# big-module-test1.net
KiCad netlist of a schematic drawn in EAGLE
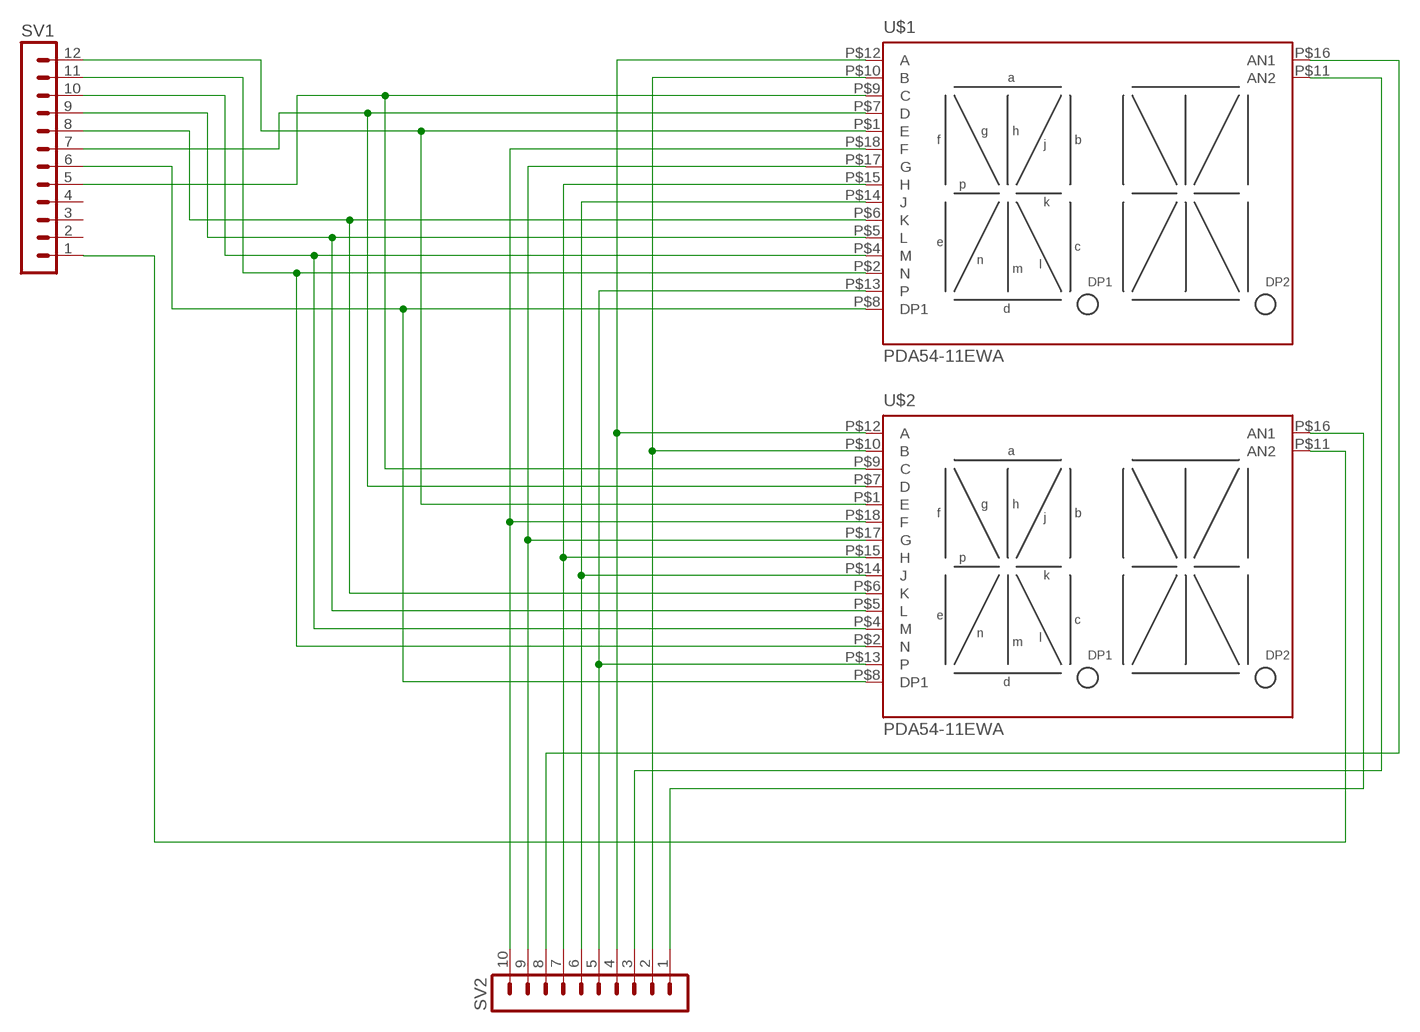
[diagram p0: schematic, sheet 1]

(export (version "E")
  (design (tool "Eeschema 10.0.6"))
  (components
    (comp (ref "SV1")
      (value "MA12-1W")
      (footprint "eagle-import:MA12-1W")
      (libsource (lib "eagle-import") (part "MA12-1W"))
    )
    (comp (ref "SV2")
      (value "MA10-1")
      (footprint "eagle-import:MA10-1")
      (libsource (lib "eagle-import") (part "MA10-1"))
    )
    (comp (ref "U$1")
      (value "PDA54-11EWA")
      (footprint "eagle-import:PDA54-11XX")
      (libsource (lib "eagle-import") (part "PDA54-11EWA"))
    )
    (comp (ref "U$2")
      (value "PDA54-11EWA")
      (footprint "eagle-import:PDA54-11XX")
      (libsource (lib "eagle-import") (part "PDA54-11EWA"))
    )
  )
  (nets
    (net (code "1") (name "Net-(U$1-A)") (class "Default")
      (node (ref "SV2") (pin "4") (pinfunction "4_4") (pintype "passive"))
      (node (ref "U$1") (pin "P$12") (pinfunction "A_P$12") (pintype "passive"))
      (node (ref "U$2") (pin "P$12") (pinfunction "A_P$12") (pintype "passive"))
    )
    (net (code "2") (name "Net-(U$1-AN1)") (class "Default")
      (node (ref "SV2") (pin "8") (pinfunction "8_8") (pintype "passive"))
      (node (ref "U$1") (pin "P$16") (pinfunction "AN1_P$16") (pintype "passive"))
    )
    (net (code "3") (name "Net-(U$1-AN2)") (class "Default")
      (node (ref "SV2") (pin "3") (pinfunction "3_3") (pintype "passive"))
      (node (ref "U$1") (pin "P$11") (pinfunction "AN2_P$11") (pintype "passive"))
    )
    (net (code "4") (name "Net-(U$1-B)") (class "Default")
      (node (ref "SV2") (pin "2") (pinfunction "2_2") (pintype "passive"))
      (node (ref "U$1") (pin "P$10") (pinfunction "B_P$10") (pintype "passive"))
      (node (ref "U$2") (pin "P$10") (pinfunction "B_P$10") (pintype "passive"))
    )
    (net (code "5") (name "Net-(U$1-C)") (class "Default")
      (node (ref "SV1") (pin "5") (pinfunction "5_5") (pintype "passive"))
      (node (ref "U$1") (pin "P$9") (pinfunction "C_P$9") (pintype "passive"))
      (node (ref "U$2") (pin "P$9") (pinfunction "C_P$9") (pintype "passive"))
    )
    (net (code "6") (name "Net-(U$1-D)") (class "Default")
      (node (ref "SV1") (pin "7") (pinfunction "7_7") (pintype "passive"))
      (node (ref "U$1") (pin "P$7") (pinfunction "D_P$7") (pintype "passive"))
      (node (ref "U$2") (pin "P$7") (pinfunction "D_P$7") (pintype "passive"))
    )
    (net (code "7") (name "Net-(U$1-DP1)") (class "Default")
      (node (ref "SV1") (pin "6") (pinfunction "6_6") (pintype "passive"))
      (node (ref "U$1") (pin "P$8") (pinfunction "DP1_P$8") (pintype "passive"))
      (node (ref "U$2") (pin "P$8") (pinfunction "DP1_P$8") (pintype "passive"))
    )
    (net (code "8") (name "Net-(U$1-E)") (class "Default")
      (node (ref "SV1") (pin "12") (pinfunction "12_12") (pintype "passive"))
      (node (ref "U$1") (pin "P$1") (pinfunction "E_P$1") (pintype "passive"))
      (node (ref "U$2") (pin "P$1") (pinfunction "E_P$1") (pintype "passive"))
    )
    (net (code "9") (name "Net-(U$1-F)") (class "Default")
      (node (ref "SV2") (pin "10") (pinfunction "10_10") (pintype "passive"))
      (node (ref "U$1") (pin "P$18") (pinfunction "F_P$18") (pintype "passive"))
      (node (ref "U$2") (pin "P$18") (pinfunction "F_P$18") (pintype "passive"))
    )
    (net (code "10") (name "Net-(U$1-G)") (class "Default")
      (node (ref "SV2") (pin "9") (pinfunction "9_9") (pintype "passive"))
      (node (ref "U$1") (pin "P$17") (pinfunction "G_P$17") (pintype "passive"))
      (node (ref "U$2") (pin "P$17") (pinfunction "G_P$17") (pintype "passive"))
    )
    (net (code "11") (name "Net-(U$1-H)") (class "Default")
      (node (ref "SV2") (pin "7") (pinfunction "7_7") (pintype "passive"))
      (node (ref "U$1") (pin "P$15") (pinfunction "H_P$15") (pintype "passive"))
      (node (ref "U$2") (pin "P$15") (pinfunction "H_P$15") (pintype "passive"))
    )
    (net (code "12") (name "Net-(U$1-J)") (class "Default")
      (node (ref "SV2") (pin "6") (pinfunction "6_6") (pintype "passive"))
      (node (ref "U$1") (pin "P$14") (pinfunction "J_P$14") (pintype "passive"))
      (node (ref "U$2") (pin "P$14") (pinfunction "J_P$14") (pintype "passive"))
    )
    (net (code "13") (name "Net-(U$1-K)") (class "Default")
      (node (ref "SV1") (pin "8") (pinfunction "8_8") (pintype "passive"))
      (node (ref "U$1") (pin "P$6") (pinfunction "K_P$6") (pintype "passive"))
      (node (ref "U$2") (pin "P$6") (pinfunction "K_P$6") (pintype "passive"))
    )
    (net (code "14") (name "Net-(U$1-L)") (class "Default")
      (node (ref "SV1") (pin "9") (pinfunction "9_9") (pintype "passive"))
      (node (ref "U$1") (pin "P$5") (pinfunction "L_P$5") (pintype "passive"))
      (node (ref "U$2") (pin "P$5") (pinfunction "L_P$5") (pintype "passive"))
    )
    (net (code "15") (name "Net-(U$1-M)") (class "Default")
      (node (ref "SV1") (pin "10") (pinfunction "10_10") (pintype "passive"))
      (node (ref "U$1") (pin "P$4") (pinfunction "M_P$4") (pintype "passive"))
      (node (ref "U$2") (pin "P$4") (pinfunction "M_P$4") (pintype "passive"))
    )
    (net (code "16") (name "Net-(U$1-N)") (class "Default")
      (node (ref "SV1") (pin "11") (pinfunction "11_11") (pintype "passive"))
      (node (ref "U$1") (pin "P$2") (pinfunction "N_P$2") (pintype "passive"))
      (node (ref "U$2") (pin "P$2") (pinfunction "N_P$2") (pintype "passive"))
    )
    (net (code "17") (name "Net-(U$1-P)") (class "Default")
      (node (ref "SV2") (pin "5") (pinfunction "5_5") (pintype "passive"))
      (node (ref "U$1") (pin "P$13") (pinfunction "P_P$13") (pintype "passive"))
      (node (ref "U$2") (pin "P$13") (pinfunction "P_P$13") (pintype "passive"))
    )
    (net (code "18") (name "Net-(U$2-AN1)") (class "Default")
      (node (ref "SV2") (pin "1") (pinfunction "1_1") (pintype "passive"))
      (node (ref "U$2") (pin "P$16") (pinfunction "AN1_P$16") (pintype "passive"))
    )
    (net (code "19") (name "Net-(U$2-AN2)") (class "Default")
      (node (ref "SV1") (pin "1") (pinfunction "1_1") (pintype "passive"))
      (node (ref "U$2") (pin "P$11") (pinfunction "AN2_P$11") (pintype "passive"))
    )
    (net (code "20") (name "unconnected-(SV1-Pad2)") (class "Default")
      (node (ref "SV1") (pin "2") (pinfunction "2_2") (pintype "passive"))
    )
    (net (code "21") (name "unconnected-(SV1-Pad3)") (class "Default")
      (node (ref "SV1") (pin "3") (pinfunction "3_3") (pintype "passive"))
    )
    (net (code "22") (name "unconnected-(SV1-Pad4)") (class "Default")
      (node (ref "SV1") (pin "4") (pinfunction "4_4") (pintype "passive"))
    )
  )
)
